# Scheme.net
KiCad netlist of a schematic drawn in Altium Designer
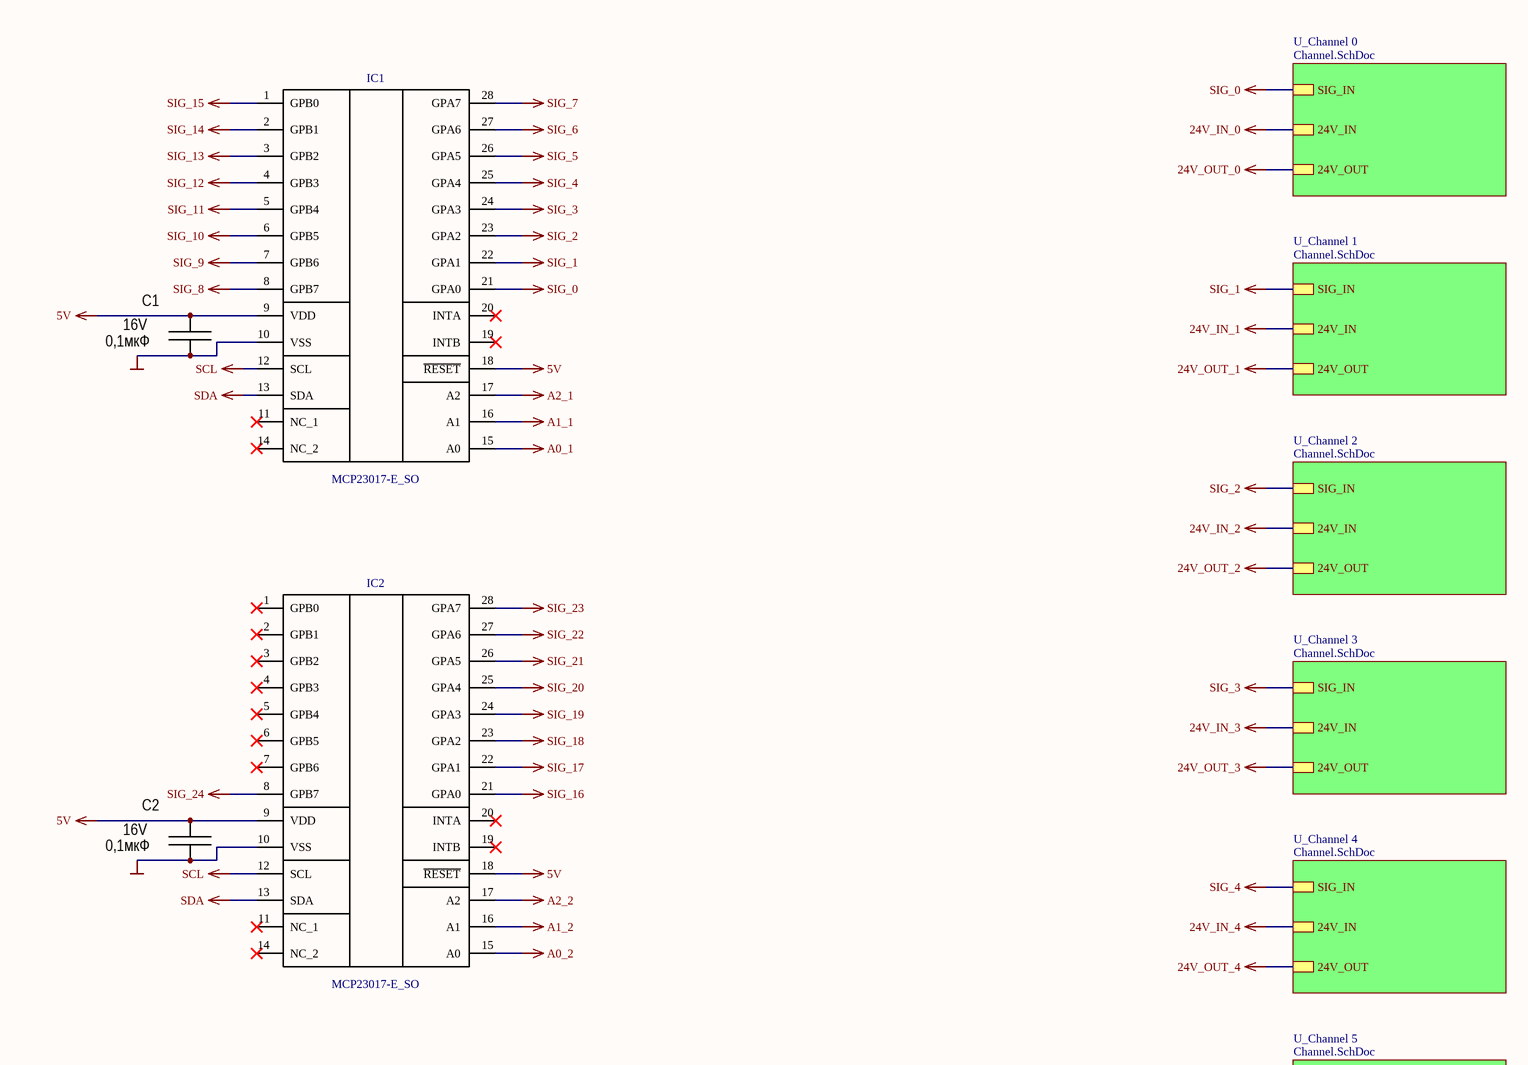
[diagram p0: Scheme.SchDoc, top left]
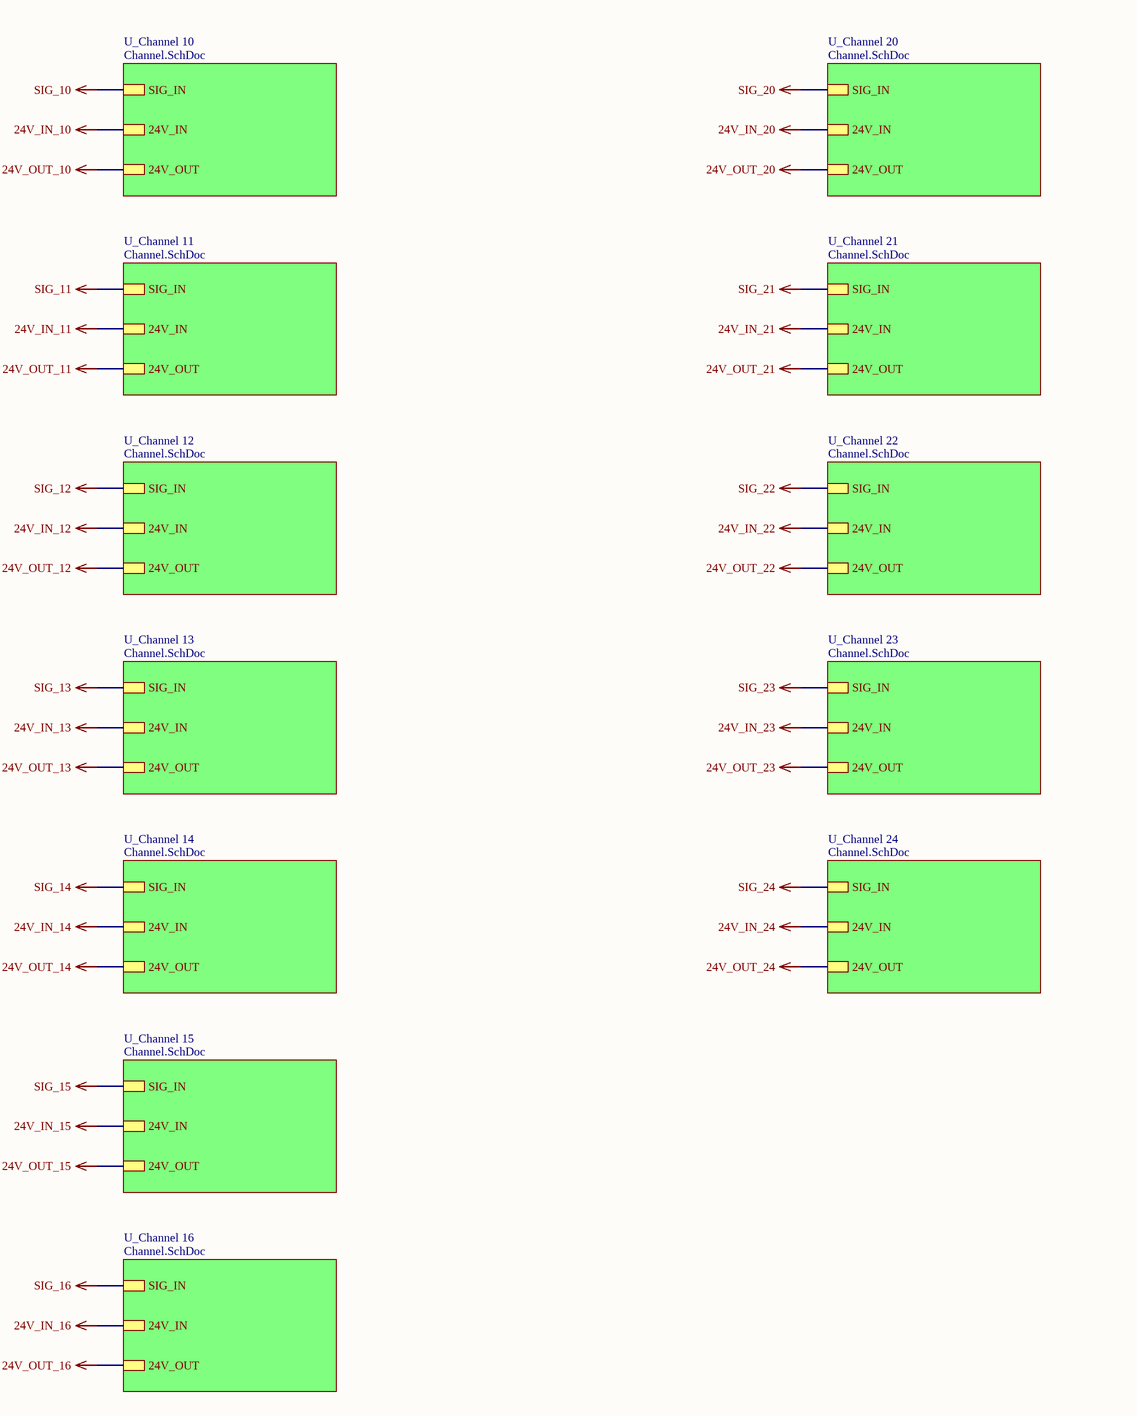
[diagram p1: Scheme.SchDoc, top right]
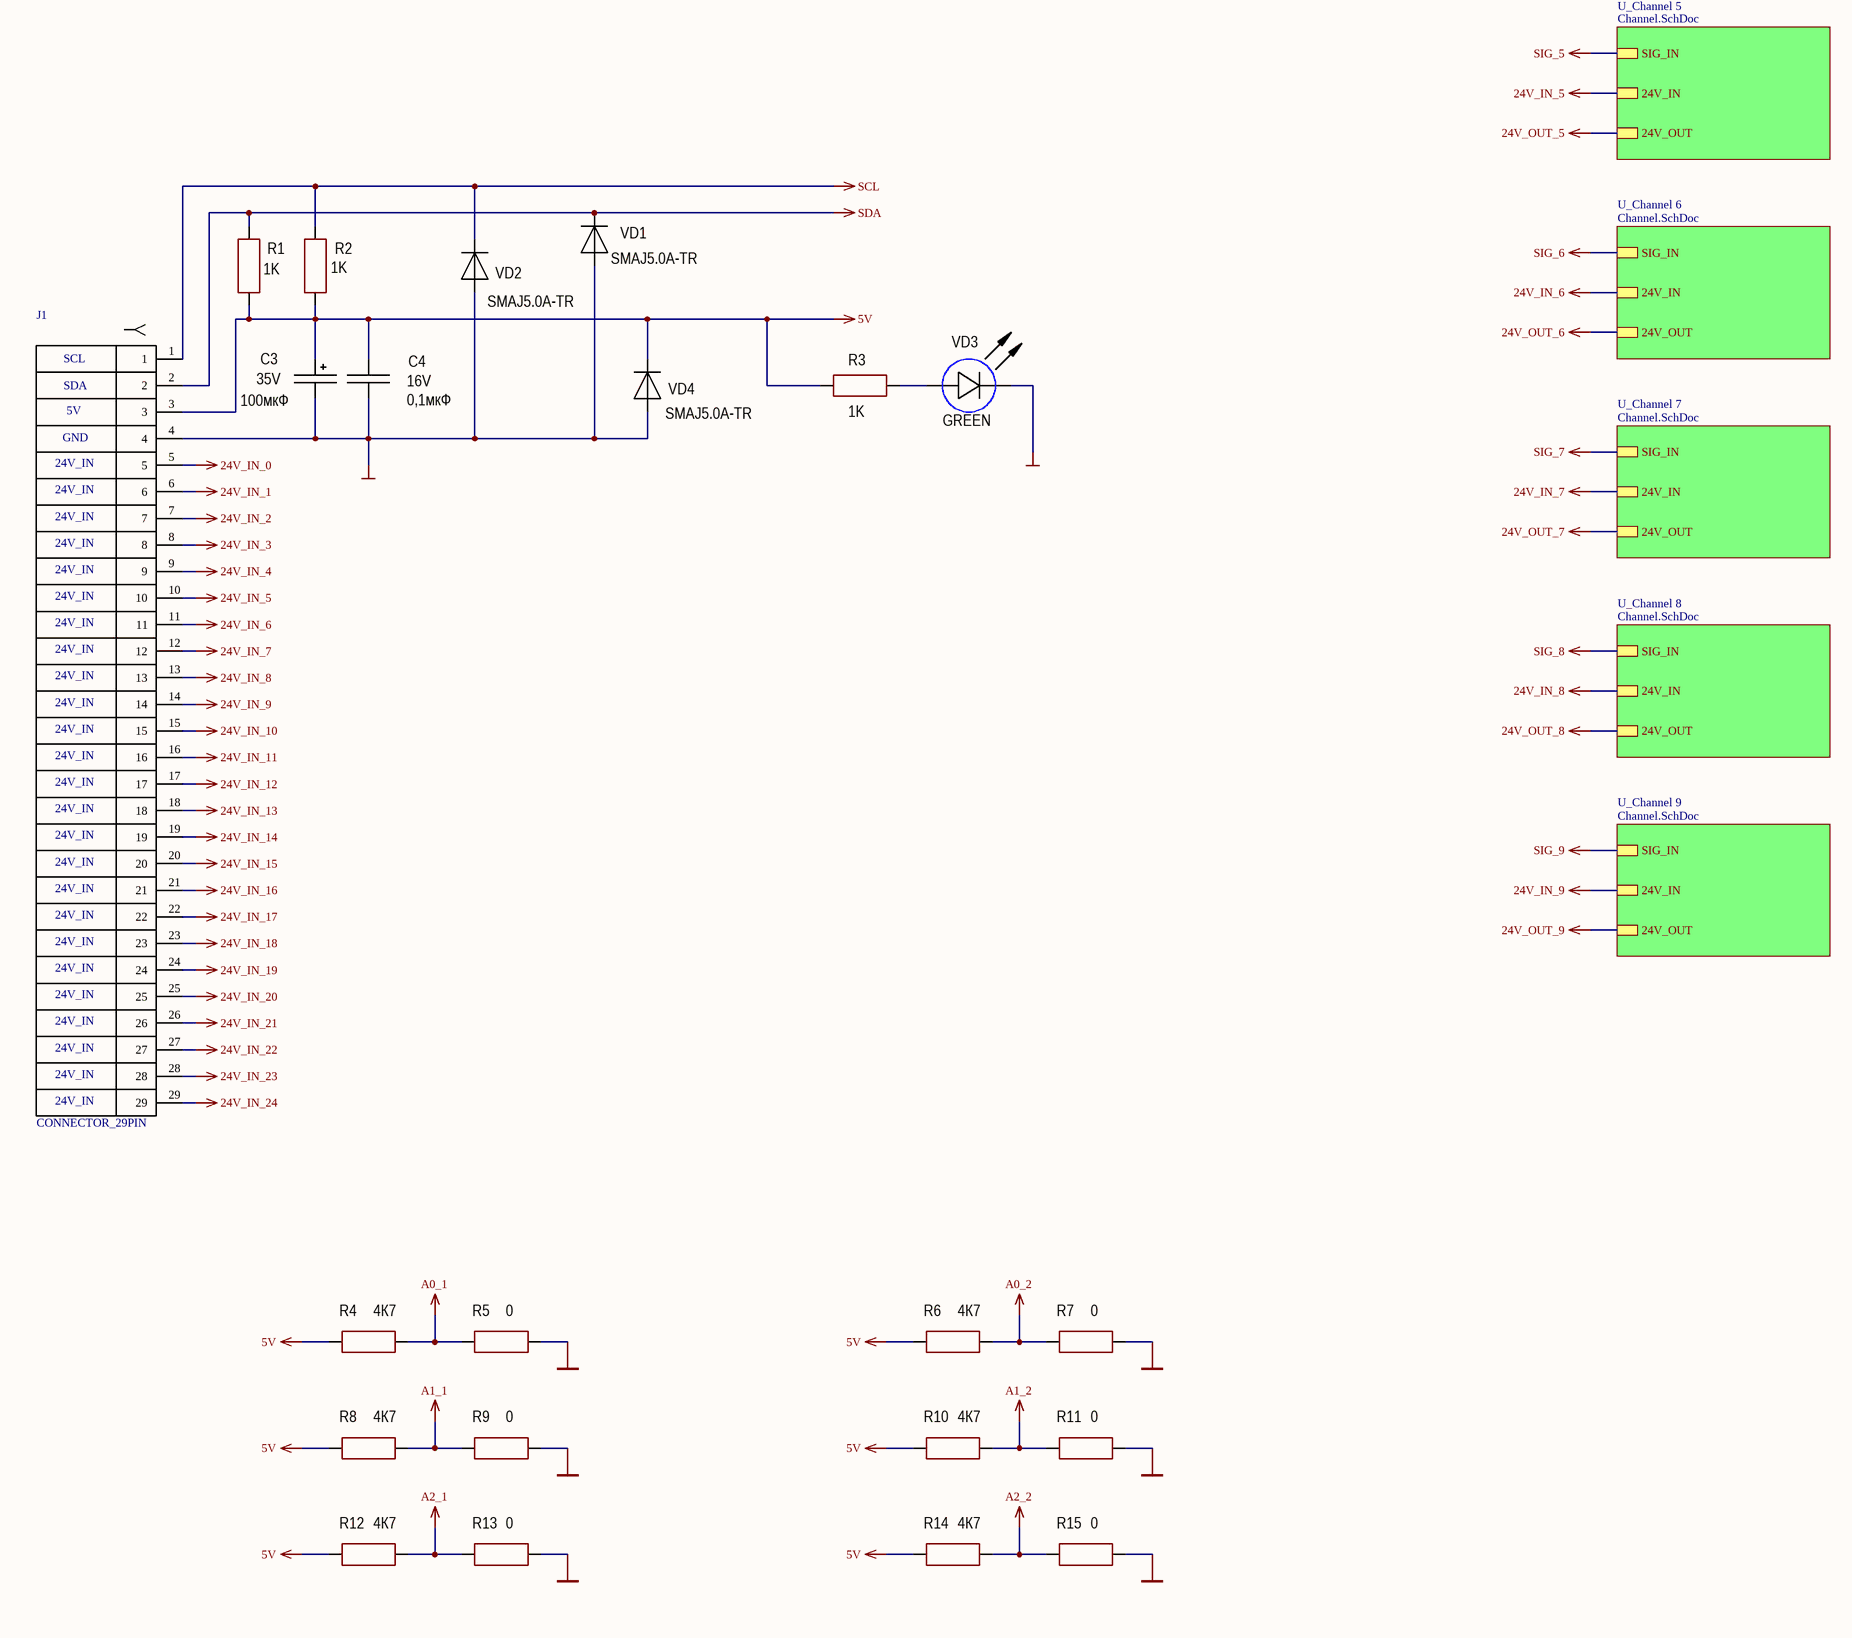
[diagram p2: Scheme.SchDoc, bottom left]
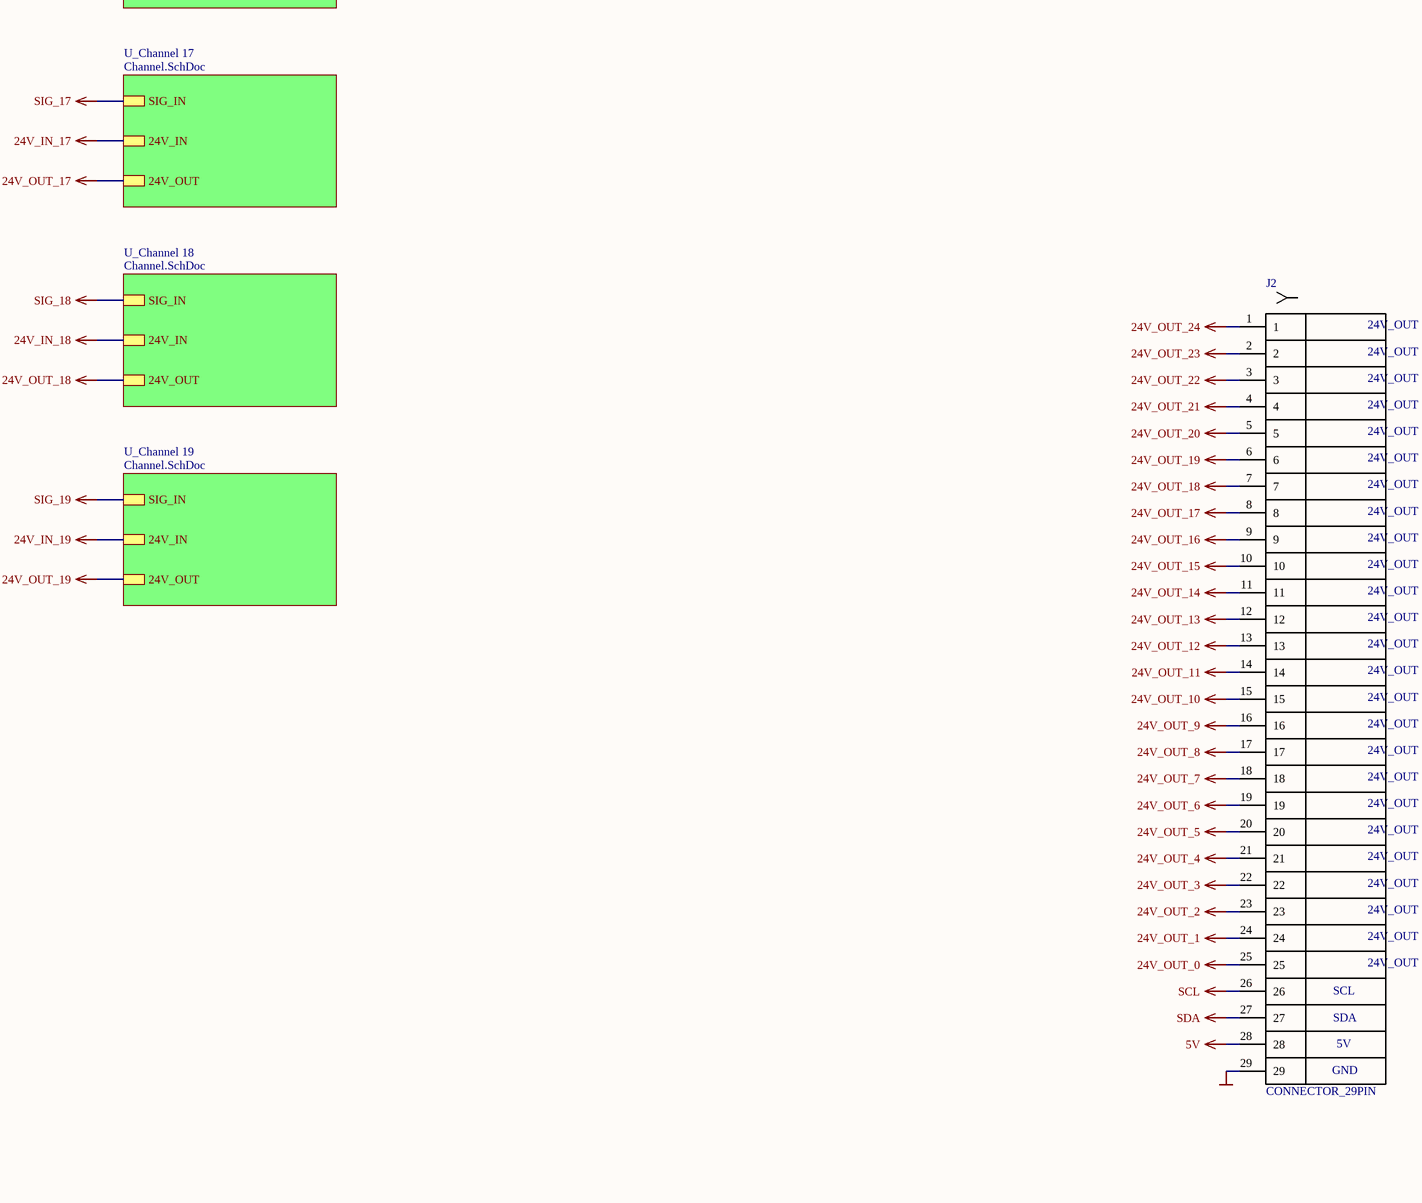
[diagram p3: Scheme.SchDoc, bottom right]

(export (version "E")
  (design (tool "Eeschema 10.0.6"))
  (components
    (comp (ref "C1")
      (value "0,1мкФ")
      (footprint "CAP: 0805")
      (fields
        (field (name "MANUFACTURER") "Yageo")
        (field (name "PARTNUMBER") "CC0805KRX7R7BB104")
        (field (name "VALUEMANUFACTURERPARTNUMBER") "Ceramic capacitor, 0,1мкФ, X7R, ±10%, 16V, 0805, -55...+125°C")
        (field (name "VOLTAGE") "16V")
      )
      (libsource (lib "Capacitor") (part "Ceramic_0805"))
    )
    (comp (ref "C2")
      (value "0,1мкФ")
      (footprint "CAP: 0805")
      (fields
        (field (name "MANUFACTURER") "Yageo")
        (field (name "PARTNUMBER") "CC0805KRX7R7BB104")
        (field (name "VALUEMANUFACTURERPARTNUMBER") "Ceramic capacitor, 0,1мкФ, X7R, ±10%, 16V, 0805, -55...+125°C")
        (field (name "VOLTAGE") "16V")
      )
      (libsource (lib "Capacitor") (part "Ceramic_0805"))
    )
    (comp (ref "C3")
      (value "100мкФ")
      (footprint "CAP: D8C3.5H12")
      (fields
        (field (name "MANUFACTURER") "Wurth")
        (field (name "PARTNUMBER") "860080475013")
        (field (name "VALUEMANUFACTURERPARTNUMBER") "Aluminium capacitor, 100мкФ, 35V, ±20%, 54mOhm, 14x10x5 mm, -55...+105°C")
        (field (name "VOLTAGE") "35V")
      )
      (libsource (lib "Capacitor") (part "Aluminium"))
    )
    (comp (ref "C4")
      (value "0,1мкФ")
      (footprint "CAP: 0805")
      (fields
        (field (name "MANUFACTURER") "Yageo")
        (field (name "PARTNUMBER") "CC0805KRX7R7BB104")
        (field (name "VALUEMANUFACTURERPARTNUMBER") "Ceramic capacitor, 0,1мкФ, X7R, ±10%, 16V, 0805, -55...+125°C")
        (field (name "VOLTAGE") "16V")
      )
      (libsource (lib "Capacitor") (part "Ceramic_0805"))
    )
    (comp (ref "IC1")
      (value "MCP23017-E_SO")
      (footprint "PcbLib:SOIC127P1030X265-28N")
      (description "Integrated Circuit")
      (fields
        (field (name "MANUFACTURER_PART_NUMBER") "MCP23017-E/SO")
        (field (name "MOUSER PART NUMBER") "579-MCP23017-E/SO")
      )
      (libsource (lib "Schlib") (part "MCP23017-E_SO"))
    )
    (comp (ref "IC2")
      (value "MCP23017-E_SO")
      (footprint "PcbLib:SOIC127P1030X265-28N")
      (description "Integrated Circuit")
      (fields
        (field (name "MANUFACTURER_PART_NUMBER") "MCP23017-E/SO")
        (field (name "MOUSER PART NUMBER") "579-MCP23017-E/SO")
      )
      (libsource (lib "Schlib") (part "MCP23017-E_SO"))
    )
    (comp (ref "J1")
      (value "CONNECTOR_29PIN")
      (footprint "Connector_29pin")
      (description "Connector 29 pin")
      (libsource (lib "") (part "CONNECTOR_29PIN_1"))
    )
    (comp (ref "J2")
      (value "CONNECTOR_29PIN")
      (footprint "Connector_29pin")
      (description "Connector 29 pin")
      (libsource (lib "Schlib") (part "CONNECTOR_29PIN"))
    )
    (comp (ref "R1")
      (value "1K")
      (footprint "RES: 0805")
      (fields
        (field (name "MANUFACTURER") "Yageo")
        (field (name "PARTNUMBER") "RC0805JR-07100RL")
        (field (name "VALUEMANUFACTURERPARTNUMBER") "Resistor film, 1K, ±5%, 0805, 0.125W, -55...+125°C")
      )
      (libsource (lib "") (part "Resistor_0805_1"))
    )
    (comp (ref "R2")
      (value "1K")
      (footprint "RES: 0805")
      (fields
        (field (name "MANUFACTURER") "Yageo")
        (field (name "PARTNUMBER") "RC0805JR-07100RL")
        (field (name "VALUEMANUFACTURERPARTNUMBER") "Resistor film, 1K, ±5%, 0805, 0.125W, -55...+125°C")
      )
      (libsource (lib "") (part "Resistor_0805_1"))
    )
    (comp (ref "R3")
      (value "1K")
      (footprint "RES: 0805")
      (fields
        (field (name "MANUFACTURER") "Yageo")
        (field (name "PARTNUMBER") "RC0805JR-07100RL")
        (field (name "VALUEMANUFACTURERPARTNUMBER") "Resistor film, 1K, ±5%, 0805, 0.125W, -55...+125°C")
      )
      (libsource (lib "") (part "Resistor_0805_1"))
    )
    (comp (ref "R4")
      (value "4К7")
      (footprint "RES: 0805")
      (fields
        (field (name "MANUFACTURER") "Yageo")
        (field (name "PARTNUMBER") "RC0805JR-07100RL")
        (field (name "VALUEMANUFACTURERPARTNUMBER") "Resistor film, 4К7, ±5%, 0805, 0.125W, -55...+125°C")
      )
      (libsource (lib "Resistor") (part "Resistor_0805"))
    )
    (comp (ref "R5")
      (value "0")
      (footprint "RES: 0805")
      (fields
        (field (name "MANUFACTURER") "Yageo")
        (field (name "PARTNUMBER") "RC0805JR-07100RL")
        (field (name "VALUEMANUFACTURERPARTNUMBER") "Resistor film, 0, ±5%, 0805, 0.125W, -55...+125°C")
      )
      (libsource (lib "Resistor") (part "Resistor_0805"))
    )
    (comp (ref "R6")
      (value "4К7")
      (footprint "RES: 0805")
      (fields
        (field (name "MANUFACTURER") "Yageo")
        (field (name "PARTNUMBER") "RC0805JR-07100RL")
        (field (name "VALUEMANUFACTURERPARTNUMBER") "Resistor film, 4К7, ±5%, 0805, 0.125W, -55...+125°C")
      )
      (libsource (lib "Resistor") (part "Resistor_0805"))
    )
    (comp (ref "R7")
      (value "0")
      (footprint "RES: 0805")
      (fields
        (field (name "MANUFACTURER") "Yageo")
        (field (name "PARTNUMBER") "RC0805JR-07100RL")
        (field (name "VALUEMANUFACTURERPARTNUMBER") "Resistor film, 0, ±5%, 0805, 0.125W, -55...+125°C")
      )
      (libsource (lib "Resistor") (part "Resistor_0805"))
    )
    (comp (ref "R8")
      (value "4К7")
      (footprint "RES: 0805")
      (fields
        (field (name "MANUFACTURER") "Yageo")
        (field (name "PARTNUMBER") "RC0805JR-07100RL")
        (field (name "VALUEMANUFACTURERPARTNUMBER") "Resistor film, 4К7, ±5%, 0805, 0.125W, -55...+125°C")
      )
      (libsource (lib "Resistor") (part "Resistor_0805"))
    )
    (comp (ref "R9")
      (value "0")
      (footprint "RES: 0805")
      (fields
        (field (name "MANUFACTURER") "Yageo")
        (field (name "PARTNUMBER") "RC0805JR-07100RL")
        (field (name "VALUEMANUFACTURERPARTNUMBER") "Resistor film, 0, ±5%, 0805, 0.125W, -55...+125°C")
      )
      (libsource (lib "Resistor") (part "Resistor_0805"))
    )
    (comp (ref "R10")
      (value "4К7")
      (footprint "RES: 0805")
      (fields
        (field (name "MANUFACTURER") "Yageo")
        (field (name "PARTNUMBER") "RC0805JR-07100RL")
        (field (name "VALUEMANUFACTURERPARTNUMBER") "Resistor film, 4К7, ±5%, 0805, 0.125W, -55...+125°C")
      )
      (libsource (lib "Resistor") (part "Resistor_0805"))
    )
    (comp (ref "R11")
      (value "0")
      (footprint "RES: 0805")
      (fields
        (field (name "MANUFACTURER") "Yageo")
        (field (name "PARTNUMBER") "RC0805JR-07100RL")
        (field (name "VALUEMANUFACTURERPARTNUMBER") "Resistor film, 0, ±5%, 0805, 0.125W, -55...+125°C")
      )
      (libsource (lib "Resistor") (part "Resistor_0805"))
    )
    (comp (ref "R12")
      (value "4К7")
      (footprint "RES: 0805")
      (fields
        (field (name "MANUFACTURER") "Yageo")
        (field (name "PARTNUMBER") "RC0805JR-07100RL")
        (field (name "VALUEMANUFACTURERPARTNUMBER") "Resistor film, 4К7, ±5%, 0805, 0.125W, -55...+125°C")
      )
      (libsource (lib "Resistor") (part "Resistor_0805"))
    )
    (comp (ref "R13")
      (value "0")
      (footprint "RES: 0805")
      (fields
        (field (name "MANUFACTURER") "Yageo")
        (field (name "PARTNUMBER") "RC0805JR-07100RL")
        (field (name "VALUEMANUFACTURERPARTNUMBER") "Resistor film, 0, ±5%, 0805, 0.125W, -55...+125°C")
      )
      (libsource (lib "Resistor") (part "Resistor_0805"))
    )
    (comp (ref "R14")
      (value "4К7")
      (footprint "RES: 0805")
      (fields
        (field (name "MANUFACTURER") "Yageo")
        (field (name "PARTNUMBER") "RC0805JR-07100RL")
        (field (name "VALUEMANUFACTURERPARTNUMBER") "Resistor film, 4К7, ±5%, 0805, 0.125W, -55...+125°C")
      )
      (libsource (lib "Resistor") (part "Resistor_0805"))
    )
    (comp (ref "R15")
      (value "0")
      (footprint "RES: 0805")
      (fields
        (field (name "MANUFACTURER") "Yageo")
        (field (name "PARTNUMBER") "RC0805JR-07100RL")
        (field (name "VALUEMANUFACTURERPARTNUMBER") "Resistor film, 0, ±5%, 0805, 0.125W, -55...+125°C")
      )
      (libsource (lib "Resistor") (part "Resistor_0805"))
    )
    (comp (ref "VD1")
      (value "~")
      (footprint "DIODE: SMA")
      (fields
        (field (name "MANUFACTURER") "Micro Commercial")
        (field (name "VALUEMANUFACTURERPARTNUMBER") "Single diode, 75V, 150mA, 1V, 4ns, SOD-323, -55...+150°C")
        (field (name "VOLTAGE") "75V")
        (field (name "PARTNUMBER") "SMAJ5.0A-TR")
      )
      (libsource (lib "Diode") (part "Diode_single"))
    )
    (comp (ref "VD2")
      (value "~")
      (footprint "DIODE: SMA")
      (fields
        (field (name "MANUFACTURER") "Micro Commercial")
        (field (name "VALUEMANUFACTURERPARTNUMBER") "Single diode, 75V, 150mA, 1V, 4ns, SOD-323, -55...+150°C")
        (field (name "VOLTAGE") "75V")
        (field (name "PARTNUMBER") "SMAJ5.0A-TR")
      )
      (libsource (lib "Diode") (part "Diode_single"))
    )
    (comp (ref "VD3")
      (value "~")
      (footprint "1224HRC5")
      (fields
        (field (name "VALUEMANUFACTURERPARTNUMBER") "LED, Green, *, *, *, -55...+150°C")
        (field (name "COLOR") "GREEN")
      )
      (libsource (lib "Diode") (part "LED_single"))
    )
    (comp (ref "VD4")
      (value "~")
      (footprint "DIODE: SMA")
      (fields
        (field (name "MANUFACTURER") "Micro Commercial")
        (field (name "VALUEMANUFACTURERPARTNUMBER") "Single diode, 75V, 150mA, 1V, 4ns, SOD-323, -55...+150°C")
        (field (name "VOLTAGE") "75V")
        (field (name "PARTNUMBER") "SMAJ5.0A-TR")
      )
      (libsource (lib "Diode") (part "Diode_single"))
    )
  )
  (nets
    (net (code "1") (name "5V") (class "Default")
      (node (ref "C1") (pin "2") (pinfunction "2_2") (pintype "power_in"))
      (node (ref "C2") (pin "2") (pinfunction "2_2") (pintype "power_in"))
      (node (ref "C3") (pin "1") (pinfunction "1_1") (pintype "power_in"))
      (node (ref "C4") (pin "2") (pinfunction "2_2") (pintype "power_in"))
      (node (ref "IC1") (pin "18") (pinfunction "~{RESET}_18") (pintype "passive"))
      (node (ref "IC1") (pin "9") (pinfunction "VDD_9") (pintype "passive"))
      (node (ref "IC2") (pin "18") (pinfunction "~{RESET}_18") (pintype "passive"))
      (node (ref "IC2") (pin "9") (pinfunction "VDD_9") (pintype "passive"))
      (node (ref "J1") (pin "3") (pinfunction "3_3") (pintype "passive"))
      (node (ref "J2") (pin "28") (pinfunction "28_28") (pintype "passive"))
      (node (ref "R1") (pin "1") (pinfunction "1_1") (pintype "passive"))
      (node (ref "R10") (pin "1") (pinfunction "1_1") (pintype "passive"))
      (node (ref "R12") (pin "1") (pinfunction "1_1") (pintype "passive"))
      (node (ref "R14") (pin "1") (pinfunction "1_1") (pintype "passive"))
      (node (ref "R2") (pin "1") (pinfunction "1_1") (pintype "passive"))
      (node (ref "R3") (pin "1") (pinfunction "1_1") (pintype "passive"))
      (node (ref "R4") (pin "1") (pinfunction "1_1") (pintype "passive"))
      (node (ref "R6") (pin "1") (pinfunction "1_1") (pintype "passive"))
      (node (ref "R8") (pin "1") (pinfunction "1_1") (pintype "passive"))
      (node (ref "VD4") (pin "2") (pinfunction "2_2") (pintype "passive"))
    )
    (net (code "2") (name "24V_IN_0") (class "Default")
      (node (ref "J1") (pin "5") (pinfunction "5_5") (pintype "passive"))
    )
    (net (code "3") (name "24V_IN_1") (class "Default")
      (node (ref "J1") (pin "6") (pinfunction "6_6") (pintype "passive"))
    )
    (net (code "4") (name "24V_IN_2") (class "Default")
      (node (ref "J1") (pin "7") (pinfunction "7_7") (pintype "passive"))
    )
    (net (code "5") (name "24V_IN_3") (class "Default")
      (node (ref "J1") (pin "8") (pinfunction "8_8") (pintype "passive"))
    )
    (net (code "6") (name "24V_IN_4") (class "Default")
      (node (ref "J1") (pin "9") (pinfunction "9_9") (pintype "passive"))
    )
    (net (code "7") (name "24V_IN_5") (class "Default")
      (node (ref "J1") (pin "10") (pinfunction "10_10") (pintype "passive"))
    )
    (net (code "8") (name "24V_IN_6") (class "Default")
      (node (ref "J1") (pin "11") (pinfunction "11_11") (pintype "passive"))
    )
    (net (code "9") (name "24V_IN_7") (class "Default")
      (node (ref "J1") (pin "12") (pinfunction "12_12") (pintype "passive"))
    )
    (net (code "10") (name "24V_IN_8") (class "Default")
      (node (ref "J1") (pin "13") (pinfunction "13_13") (pintype "passive"))
    )
    (net (code "11") (name "24V_IN_9") (class "Default")
      (node (ref "J1") (pin "14") (pinfunction "14_14") (pintype "passive"))
    )
    (net (code "12") (name "24V_IN_10") (class "Default")
      (node (ref "J1") (pin "15") (pinfunction "15_15") (pintype "passive"))
    )
    (net (code "13") (name "24V_IN_11") (class "Default")
      (node (ref "J1") (pin "16") (pinfunction "16_16") (pintype "passive"))
    )
    (net (code "14") (name "24V_IN_12") (class "Default")
      (node (ref "J1") (pin "17") (pinfunction "17_17") (pintype "passive"))
    )
    (net (code "15") (name "24V_IN_13") (class "Default")
      (node (ref "J1") (pin "18") (pinfunction "18_18") (pintype "passive"))
    )
    (net (code "16") (name "24V_IN_14") (class "Default")
      (node (ref "J1") (pin "19") (pinfunction "19_19") (pintype "passive"))
    )
    (net (code "17") (name "24V_IN_15") (class "Default")
      (node (ref "J1") (pin "20") (pinfunction "20_20") (pintype "passive"))
    )
    (net (code "18") (name "24V_IN_16") (class "Default")
      (node (ref "J1") (pin "21") (pinfunction "21_21") (pintype "passive"))
    )
    (net (code "19") (name "24V_IN_17") (class "Default")
      (node (ref "J1") (pin "22") (pinfunction "22_22") (pintype "passive"))
    )
    (net (code "20") (name "24V_IN_18") (class "Default")
      (node (ref "J1") (pin "23") (pinfunction "23_23") (pintype "passive"))
    )
    (net (code "21") (name "24V_IN_19") (class "Default")
      (node (ref "J1") (pin "24") (pinfunction "24_24") (pintype "passive"))
    )
    (net (code "22") (name "24V_IN_20") (class "Default")
      (node (ref "J1") (pin "25") (pinfunction "25_25") (pintype "passive"))
    )
    (net (code "23") (name "24V_IN_21") (class "Default")
      (node (ref "J1") (pin "26") (pinfunction "26_26") (pintype "passive"))
    )
    (net (code "24") (name "24V_IN_22") (class "Default")
      (node (ref "J1") (pin "27") (pinfunction "27_27") (pintype "passive"))
    )
    (net (code "25") (name "24V_IN_23") (class "Default")
      (node (ref "J1") (pin "28") (pinfunction "28_28") (pintype "passive"))
    )
    (net (code "26") (name "24V_IN_24") (class "Default")
      (node (ref "J1") (pin "29") (pinfunction "29_29") (pintype "passive"))
    )
    (net (code "27") (name "24V_OUT_0") (class "Default")
      (node (ref "J2") (pin "25") (pinfunction "25_25") (pintype "passive"))
    )
    (net (code "28") (name "24V_OUT_1") (class "Default")
      (node (ref "J2") (pin "24") (pinfunction "24_24") (pintype "passive"))
    )
    (net (code "29") (name "24V_OUT_2") (class "Default")
      (node (ref "J2") (pin "23") (pinfunction "23_23") (pintype "passive"))
    )
    (net (code "30") (name "24V_OUT_3") (class "Default")
      (node (ref "J2") (pin "22") (pinfunction "22_22") (pintype "passive"))
    )
    (net (code "31") (name "24V_OUT_4") (class "Default")
      (node (ref "J2") (pin "21") (pinfunction "21_21") (pintype "passive"))
    )
    (net (code "32") (name "24V_OUT_5") (class "Default")
      (node (ref "J2") (pin "20") (pinfunction "20_20") (pintype "passive"))
    )
    (net (code "33") (name "24V_OUT_6") (class "Default")
      (node (ref "J2") (pin "19") (pinfunction "19_19") (pintype "passive"))
    )
    (net (code "34") (name "24V_OUT_7") (class "Default")
      (node (ref "J2") (pin "18") (pinfunction "18_18") (pintype "passive"))
    )
    (net (code "35") (name "24V_OUT_8") (class "Default")
      (node (ref "J2") (pin "17") (pinfunction "17_17") (pintype "passive"))
    )
    (net (code "36") (name "24V_OUT_9") (class "Default")
      (node (ref "J2") (pin "16") (pinfunction "16_16") (pintype "passive"))
    )
    (net (code "37") (name "24V_OUT_10") (class "Default")
      (node (ref "J2") (pin "15") (pinfunction "15_15") (pintype "passive"))
    )
    (net (code "38") (name "24V_OUT_11") (class "Default")
      (node (ref "J2") (pin "14") (pinfunction "14_14") (pintype "passive"))
    )
    (net (code "39") (name "24V_OUT_12") (class "Default")
      (node (ref "J2") (pin "13") (pinfunction "13_13") (pintype "passive"))
    )
    (net (code "40") (name "24V_OUT_13") (class "Default")
      (node (ref "J2") (pin "12") (pinfunction "12_12") (pintype "passive"))
    )
    (net (code "41") (name "24V_OUT_14") (class "Default")
      (node (ref "J2") (pin "11") (pinfunction "11_11") (pintype "passive"))
    )
    (net (code "42") (name "24V_OUT_15") (class "Default")
      (node (ref "J2") (pin "10") (pinfunction "10_10") (pintype "passive"))
    )
    (net (code "43") (name "24V_OUT_16") (class "Default")
      (node (ref "J2") (pin "9") (pinfunction "9_9") (pintype "passive"))
    )
    (net (code "44") (name "24V_OUT_17") (class "Default")
      (node (ref "J2") (pin "8") (pinfunction "8_8") (pintype "passive"))
    )
    (net (code "45") (name "24V_OUT_18") (class "Default")
      (node (ref "J2") (pin "7") (pinfunction "7_7") (pintype "passive"))
    )
    (net (code "46") (name "24V_OUT_19") (class "Default")
      (node (ref "J2") (pin "6") (pinfunction "6_6") (pintype "passive"))
    )
    (net (code "47") (name "24V_OUT_20") (class "Default")
      (node (ref "J2") (pin "5") (pinfunction "5_5") (pintype "passive"))
    )
    (net (code "48") (name "24V_OUT_21") (class "Default")
      (node (ref "J2") (pin "4") (pinfunction "4_4") (pintype "passive"))
    )
    (net (code "49") (name "24V_OUT_22") (class "Default")
      (node (ref "J2") (pin "3") (pinfunction "3_3") (pintype "passive"))
    )
    (net (code "50") (name "24V_OUT_23") (class "Default")
      (node (ref "J2") (pin "2") (pinfunction "2_2") (pintype "passive"))
    )
    (net (code "51") (name "24V_OUT_24") (class "Default")
      (node (ref "J2") (pin "1") (pinfunction "1_1") (pintype "passive"))
    )
    (net (code "52") (name "A0_1") (class "Default")
      (node (ref "IC1") (pin "15") (pinfunction "A0_15") (pintype "passive"))
      (node (ref "R4") (pin "2") (pinfunction "2_2") (pintype "passive"))
      (node (ref "R5") (pin "1") (pinfunction "1_1") (pintype "passive"))
    )
    (net (code "53") (name "A0_2") (class "Default")
      (node (ref "IC2") (pin "15") (pinfunction "A0_15") (pintype "passive"))
      (node (ref "R6") (pin "2") (pinfunction "2_2") (pintype "passive"))
      (node (ref "R7") (pin "1") (pinfunction "1_1") (pintype "passive"))
    )
    (net (code "54") (name "A1_1") (class "Default")
      (node (ref "IC1") (pin "16") (pinfunction "A1_16") (pintype "passive"))
      (node (ref "R8") (pin "2") (pinfunction "2_2") (pintype "passive"))
      (node (ref "R9") (pin "1") (pinfunction "1_1") (pintype "passive"))
    )
    (net (code "55") (name "A1_2") (class "Default")
      (node (ref "IC2") (pin "16") (pinfunction "A1_16") (pintype "passive"))
      (node (ref "R10") (pin "2") (pinfunction "2_2") (pintype "passive"))
      (node (ref "R11") (pin "1") (pinfunction "1_1") (pintype "passive"))
    )
    (net (code "56") (name "A2_1") (class "Default")
      (node (ref "IC1") (pin "17") (pinfunction "A2_17") (pintype "passive"))
      (node (ref "R12") (pin "2") (pinfunction "2_2") (pintype "passive"))
      (node (ref "R13") (pin "1") (pinfunction "1_1") (pintype "passive"))
    )
    (net (code "57") (name "A2_2") (class "Default")
      (node (ref "IC2") (pin "17") (pinfunction "A2_17") (pintype "passive"))
      (node (ref "R14") (pin "2") (pinfunction "2_2") (pintype "passive"))
      (node (ref "R15") (pin "1") (pinfunction "1_1") (pintype "passive"))
    )
    (net (code "58") (name "GND") (class "Default")
      (node (ref "C1") (pin "1") (pinfunction "1_1") (pintype "power_in"))
      (node (ref "C2") (pin "1") (pinfunction "1_1") (pintype "power_in"))
      (node (ref "C3") (pin "2") (pinfunction "2_2") (pintype "power_in"))
      (node (ref "C4") (pin "1") (pinfunction "1_1") (pintype "power_in"))
      (node (ref "IC1") (pin "10") (pinfunction "VSS_10") (pintype "passive"))
      (node (ref "IC2") (pin "10") (pinfunction "VSS_10") (pintype "passive"))
      (node (ref "J1") (pin "4") (pinfunction "4_4") (pintype "passive"))
      (node (ref "J2") (pin "29") (pinfunction "29_29") (pintype "passive"))
      (node (ref "R11") (pin "2") (pinfunction "2_2") (pintype "passive"))
      (node (ref "R13") (pin "2") (pinfunction "2_2") (pintype "passive"))
      (node (ref "R15") (pin "2") (pinfunction "2_2") (pintype "passive"))
      (node (ref "R5") (pin "2") (pinfunction "2_2") (pintype "passive"))
      (node (ref "R7") (pin "2") (pinfunction "2_2") (pintype "passive"))
      (node (ref "R9") (pin "2") (pinfunction "2_2") (pintype "passive"))
      (node (ref "VD1") (pin "1") (pinfunction "1_1") (pintype "passive"))
      (node (ref "VD2") (pin "1") (pinfunction "1_1") (pintype "passive"))
      (node (ref "VD3") (pin "2") (pinfunction "C_2") (pintype "passive"))
      (node (ref "VD4") (pin "1") (pinfunction "1_1") (pintype "passive"))
    )
    (net (code "59") (name "Net-(VD3-A)") (class "Default")
      (node (ref "R3") (pin "2") (pinfunction "2_2") (pintype "passive"))
      (node (ref "VD3") (pin "1") (pinfunction "A_1") (pintype "passive"))
    )
    (net (code "60") (name "SCL") (class "Default")
      (node (ref "IC1") (pin "12") (pinfunction "SCL_12") (pintype "passive"))
      (node (ref "IC2") (pin "12") (pinfunction "SCL_12") (pintype "passive"))
      (node (ref "J1") (pin "1") (pinfunction "1_1") (pintype "passive"))
      (node (ref "J2") (pin "26") (pinfunction "26_26") (pintype "passive"))
      (node (ref "R2") (pin "2") (pinfunction "2_2") (pintype "passive"))
      (node (ref "VD2") (pin "2") (pinfunction "2_2") (pintype "passive"))
    )
    (net (code "61") (name "SDA") (class "Default")
      (node (ref "IC1") (pin "13") (pinfunction "SDA_13") (pintype "passive"))
      (node (ref "IC2") (pin "13") (pinfunction "SDA_13") (pintype "passive"))
      (node (ref "J1") (pin "2") (pinfunction "2_2") (pintype "passive"))
      (node (ref "J2") (pin "27") (pinfunction "27_27") (pintype "passive"))
      (node (ref "R1") (pin "2") (pinfunction "2_2") (pintype "passive"))
      (node (ref "VD1") (pin "2") (pinfunction "2_2") (pintype "passive"))
    )
    (net (code "62") (name "SIG_0") (class "Default")
      (node (ref "IC1") (pin "21") (pinfunction "GPA0_21") (pintype "passive"))
    )
    (net (code "63") (name "SIG_1") (class "Default")
      (node (ref "IC1") (pin "22") (pinfunction "GPA1_22") (pintype "passive"))
    )
    (net (code "64") (name "SIG_2") (class "Default")
      (node (ref "IC1") (pin "23") (pinfunction "GPA2_23") (pintype "passive"))
    )
    (net (code "65") (name "SIG_3") (class "Default")
      (node (ref "IC1") (pin "24") (pinfunction "GPA3_24") (pintype "passive"))
    )
    (net (code "66") (name "SIG_4") (class "Default")
      (node (ref "IC1") (pin "25") (pinfunction "GPA4_25") (pintype "passive"))
    )
    (net (code "67") (name "SIG_5") (class "Default")
      (node (ref "IC1") (pin "26") (pinfunction "GPA5_26") (pintype "passive"))
    )
    (net (code "68") (name "SIG_6") (class "Default")
      (node (ref "IC1") (pin "27") (pinfunction "GPA6_27") (pintype "passive"))
    )
    (net (code "69") (name "SIG_7") (class "Default")
      (node (ref "IC1") (pin "28") (pinfunction "GPA7_28") (pintype "passive"))
    )
    (net (code "70") (name "SIG_8") (class "Default")
      (node (ref "IC1") (pin "8") (pinfunction "GPB7_8") (pintype "passive"))
    )
    (net (code "71") (name "SIG_9") (class "Default")
      (node (ref "IC1") (pin "7") (pinfunction "GPB6_7") (pintype "passive"))
    )
    (net (code "72") (name "SIG_10") (class "Default")
      (node (ref "IC1") (pin "6") (pinfunction "GPB5_6") (pintype "passive"))
    )
    (net (code "73") (name "SIG_11") (class "Default")
      (node (ref "IC1") (pin "5") (pinfunction "GPB4_5") (pintype "passive"))
    )
    (net (code "74") (name "SIG_12") (class "Default")
      (node (ref "IC1") (pin "4") (pinfunction "GPB3_4") (pintype "passive"))
    )
    (net (code "75") (name "SIG_13") (class "Default")
      (node (ref "IC1") (pin "3") (pinfunction "GPB2_3") (pintype "passive"))
    )
    (net (code "76") (name "SIG_14") (class "Default")
      (node (ref "IC1") (pin "2") (pinfunction "GPB1_2") (pintype "passive"))
    )
    (net (code "77") (name "SIG_15") (class "Default")
      (node (ref "IC1") (pin "1") (pinfunction "GPB0_1") (pintype "passive"))
    )
    (net (code "78") (name "SIG_16") (class "Default")
      (node (ref "IC2") (pin "21") (pinfunction "GPA0_21") (pintype "passive"))
    )
    (net (code "79") (name "SIG_17") (class "Default")
      (node (ref "IC2") (pin "22") (pinfunction "GPA1_22") (pintype "passive"))
    )
    (net (code "80") (name "SIG_18") (class "Default")
      (node (ref "IC2") (pin "23") (pinfunction "GPA2_23") (pintype "passive"))
    )
    (net (code "81") (name "SIG_19") (class "Default")
      (node (ref "IC2") (pin "24") (pinfunction "GPA3_24") (pintype "passive"))
    )
    (net (code "82") (name "SIG_20") (class "Default")
      (node (ref "IC2") (pin "25") (pinfunction "GPA4_25") (pintype "passive"))
    )
    (net (code "83") (name "SIG_21") (class "Default")
      (node (ref "IC2") (pin "26") (pinfunction "GPA5_26") (pintype "passive"))
    )
    (net (code "84") (name "SIG_22") (class "Default")
      (node (ref "IC2") (pin "27") (pinfunction "GPA6_27") (pintype "passive"))
    )
    (net (code "85") (name "SIG_23") (class "Default")
      (node (ref "IC2") (pin "28") (pinfunction "GPA7_28") (pintype "passive"))
    )
    (net (code "86") (name "SIG_24") (class "Default")
      (node (ref "IC2") (pin "8") (pinfunction "GPB7_8") (pintype "passive"))
    )
    (net (code "87") (name "unconnected-(IC1-INTA-Pad20)") (class "Default")
      (node (ref "IC1") (pin "20") (pinfunction "INTA_20") (pintype "passive+no_connect"))
    )
    (net (code "88") (name "unconnected-(IC1-INTB-Pad19)") (class "Default")
      (node (ref "IC1") (pin "19") (pinfunction "INTB_19") (pintype "passive+no_connect"))
    )
    (net (code "89") (name "unconnected-(IC1-NC_1-Pad11)") (class "Default")
      (node (ref "IC1") (pin "11") (pinfunction "NC_1_11") (pintype "passive+no_connect"))
    )
    (net (code "90") (name "unconnected-(IC1-NC_2-Pad14)") (class "Default")
      (node (ref "IC1") (pin "14") (pinfunction "NC_2_14") (pintype "passive+no_connect"))
    )
    (net (code "91") (name "unconnected-(IC2-GPB0-Pad1)") (class "Default")
      (node (ref "IC2") (pin "1") (pinfunction "GPB0_1") (pintype "passive+no_connect"))
    )
    (net (code "92") (name "unconnected-(IC2-GPB1-Pad2)") (class "Default")
      (node (ref "IC2") (pin "2") (pinfunction "GPB1_2") (pintype "passive+no_connect"))
    )
    (net (code "93") (name "unconnected-(IC2-GPB2-Pad3)") (class "Default")
      (node (ref "IC2") (pin "3") (pinfunction "GPB2_3") (pintype "passive+no_connect"))
    )
    (net (code "94") (name "unconnected-(IC2-GPB3-Pad4)") (class "Default")
      (node (ref "IC2") (pin "4") (pinfunction "GPB3_4") (pintype "passive+no_connect"))
    )
    (net (code "95") (name "unconnected-(IC2-GPB4-Pad5)") (class "Default")
      (node (ref "IC2") (pin "5") (pinfunction "GPB4_5") (pintype "passive+no_connect"))
    )
    (net (code "96") (name "unconnected-(IC2-GPB5-Pad6)") (class "Default")
      (node (ref "IC2") (pin "6") (pinfunction "GPB5_6") (pintype "passive+no_connect"))
    )
    (net (code "97") (name "unconnected-(IC2-GPB6-Pad7)") (class "Default")
      (node (ref "IC2") (pin "7") (pinfunction "GPB6_7") (pintype "passive+no_connect"))
    )
    (net (code "98") (name "unconnected-(IC2-INTA-Pad20)") (class "Default")
      (node (ref "IC2") (pin "20") (pinfunction "INTA_20") (pintype "passive+no_connect"))
    )
    (net (code "99") (name "unconnected-(IC2-INTB-Pad19)") (class "Default")
      (node (ref "IC2") (pin "19") (pinfunction "INTB_19") (pintype "passive+no_connect"))
    )
    (net (code "100") (name "unconnected-(IC2-NC_1-Pad11)") (class "Default")
      (node (ref "IC2") (pin "11") (pinfunction "NC_1_11") (pintype "passive+no_connect"))
    )
    (net (code "101") (name "unconnected-(IC2-NC_2-Pad14)") (class "Default")
      (node (ref "IC2") (pin "14") (pinfunction "NC_2_14") (pintype "passive+no_connect"))
    )
  )
)
